# voiture.net
KiCad netlist of a schematic drawn in EAGLE
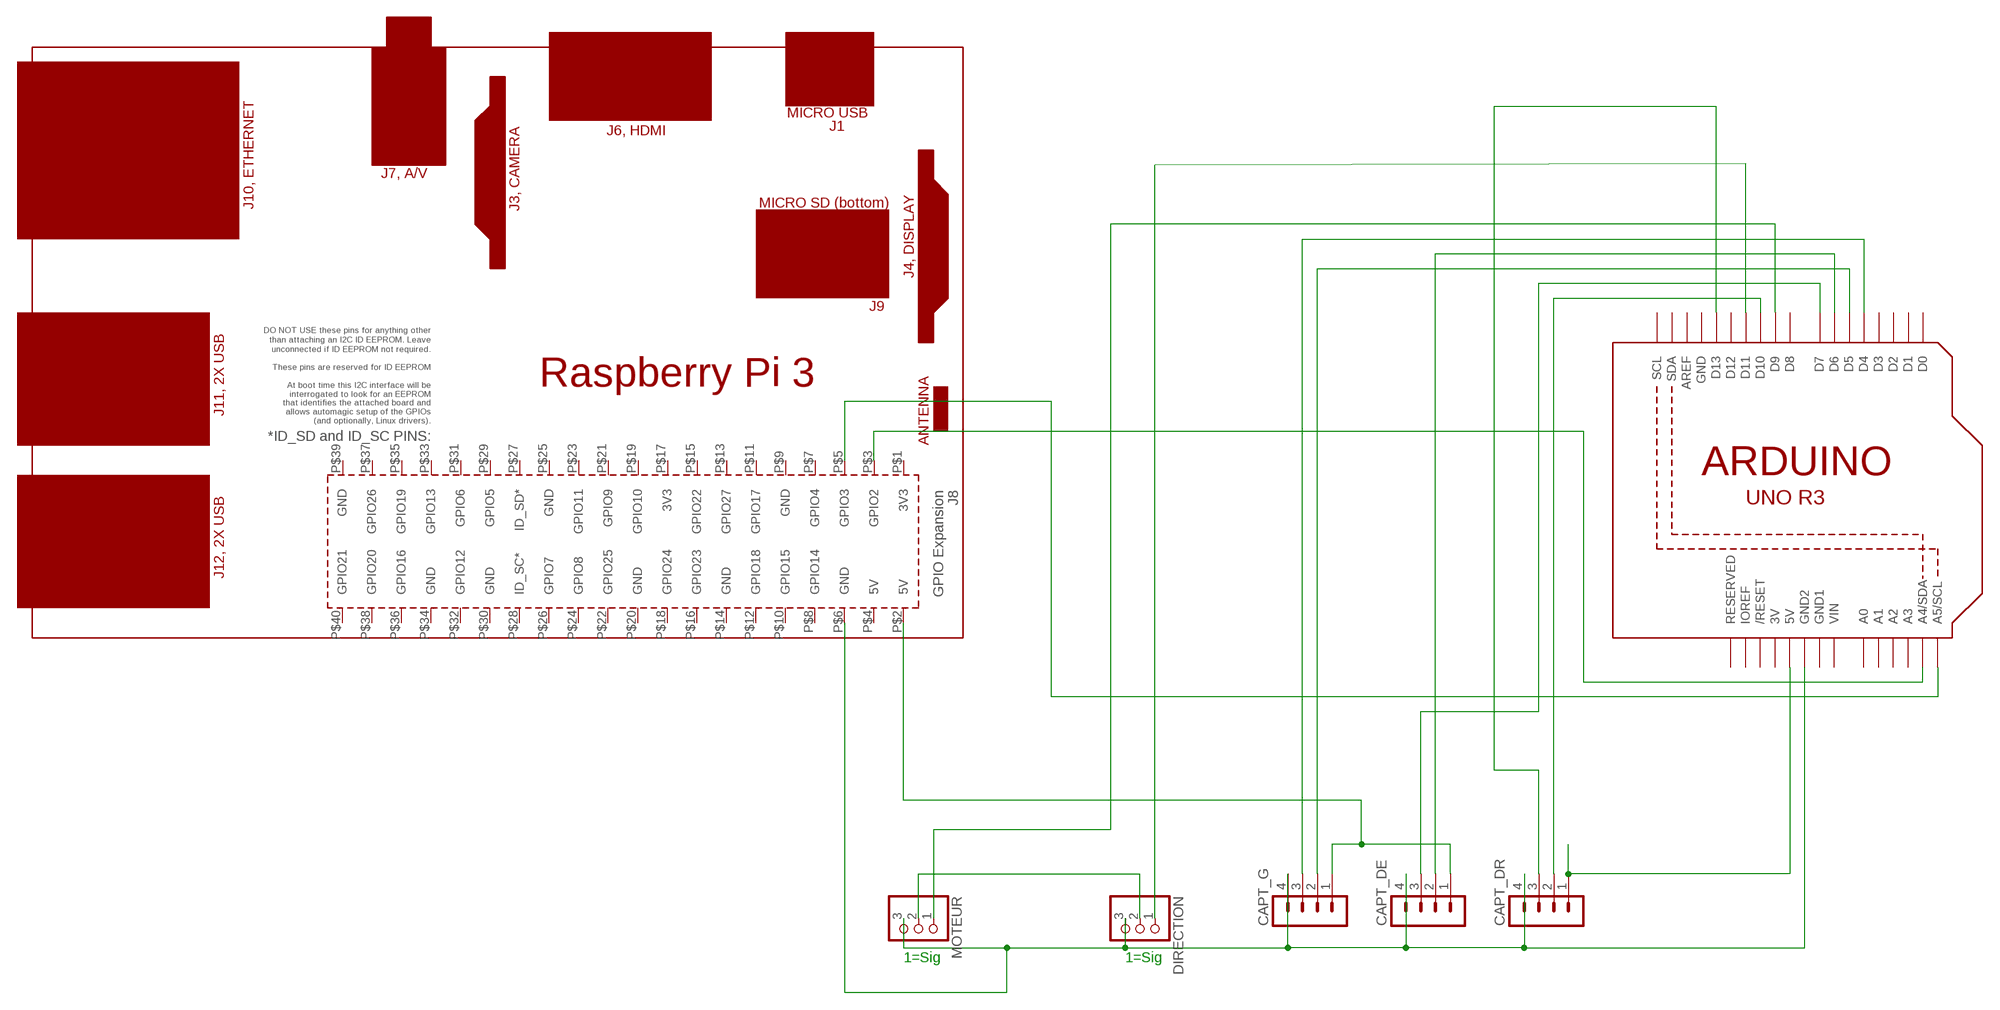
[diagram p0: schematic, sheet 1]

(export (version "E")
  (design (tool "Eeschema 10.0.6"))
  (components
    (comp (ref "CAPT_DE")
      (value "MA04-1")
      (footprint "eagle-import:MA04-1")
      (libsource (lib "eagle-import") (part "MA04-1"))
    )
    (comp (ref "CAPT_DR")
      (value "MA04-1")
      (footprint "eagle-import:MA04-1")
      (libsource (lib "eagle-import") (part "MA04-1"))
    )
    (comp (ref "CAPT_G")
      (value "MA04-1")
      (footprint "eagle-import:MA04-1")
      (libsource (lib "eagle-import") (part "MA04-1"))
    )
    (comp (ref "DIRECTION")
      (value "PINHD-1X3")
      (footprint "eagle-import:1X03")
      (libsource (lib "eagle-import") (part "PINHD-1X3"))
    )
    (comp (ref "MOTEUR")
      (value "PINHD-1X3")
      (footprint "eagle-import:1X03")
      (libsource (lib "eagle-import") (part "PINHD-1X3"))
    )
    (comp (ref "PCB1")
      (value "RPI3")
      (footprint "eagle-import:RPI3")
      (libsource (lib "eagle-import") (part "RPI3"))
    )
    (comp (ref "U1")
      (value "ARDUINOR3-BPLACE")
      (footprint "eagle-import:ARDUINOR3-BPLACE")
      (libsource (lib "eagle-import") (part "ARDUINOR3-BPLACE"))
    )
  )
  (nets
    (net (code "1") (name "/3V") (class "Default")
      (node (ref "U1") (pin "3V") (pinfunction "3V_3V") (pintype "power_in"))
    )
    (net (code "2") (name "/GND") (class "Default")
      (node (ref "U1") (pin "GND") (pinfunction "GND_GND") (pintype "power_in"))
    )
    (net (code "3") (name "/GND1") (class "Default")
      (node (ref "U1") (pin "GND1") (pinfunction "GND1_GND1") (pintype "power_in"))
    )
    (net (code "4") (name "/VIN") (class "Default")
      (node (ref "U1") (pin "VIN") (pinfunction "VIN_VIN") (pintype "power_in"))
    )
    (net (code "5") (name "Net-(CAPT_DE-Pad1)") (class "Default")
      (node (ref "CAPT_DE") (pin "1") (pinfunction "1_1") (pintype "passive"))
      (node (ref "CAPT_G") (pin "1") (pinfunction "1_1") (pintype "passive"))
      (node (ref "PCB1") (pin "P$2") (pinfunction "5V_P$2") (pintype "bidirectional"))
    )
    (net (code "6") (name "Net-(CAPT_DE-Pad2)") (class "Default")
      (node (ref "CAPT_DE") (pin "2") (pinfunction "2_2") (pintype "passive"))
      (node (ref "U1") (pin "D6") (pinfunction "D6_D6") (pintype "bidirectional"))
    )
    (net (code "7") (name "Net-(CAPT_DE-Pad3)") (class "Default")
      (node (ref "CAPT_DE") (pin "3") (pinfunction "3_3") (pintype "passive"))
      (node (ref "U1") (pin "D7") (pinfunction "D7_D7") (pintype "bidirectional"))
    )
    (net (code "8") (name "Net-(CAPT_DE-Pad4)") (class "Default")
      (node (ref "CAPT_DE") (pin "4") (pinfunction "4_4") (pintype "passive"))
      (node (ref "CAPT_DR") (pin "4") (pinfunction "4_4") (pintype "passive"))
      (node (ref "CAPT_G") (pin "4") (pinfunction "4_4") (pintype "passive"))
      (node (ref "DIRECTION") (pin "3") (pinfunction "3_3") (pintype "passive"))
      (node (ref "MOTEUR") (pin "3") (pinfunction "3_3") (pintype "passive"))
      (node (ref "PCB1") (pin "P$6") (pinfunction "GND_P$6") (pintype "bidirectional"))
      (node (ref "U1") (pin "GND2") (pinfunction "GND2_GND2") (pintype "power_in"))
    )
    (net (code "9") (name "Net-(CAPT_DR-Pad1)") (class "Default")
      (node (ref "CAPT_DR") (pin "1") (pinfunction "1_1") (pintype "passive"))
      (node (ref "U1") (pin "5V") (pinfunction "5V_5V") (pintype "power_in"))
    )
    (net (code "10") (name "Net-(CAPT_DR-Pad2)") (class "Default")
      (node (ref "CAPT_DR") (pin "2") (pinfunction "2_2") (pintype "passive"))
      (node (ref "U1") (pin "D10") (pinfunction "D10_D10") (pintype "bidirectional"))
    )
    (net (code "11") (name "Net-(CAPT_DR-Pad3)") (class "Default")
      (node (ref "CAPT_DR") (pin "3") (pinfunction "3_3") (pintype "passive"))
      (node (ref "U1") (pin "D13") (pinfunction "D13_D13") (pintype "bidirectional"))
    )
    (net (code "12") (name "Net-(CAPT_G-Pad2)") (class "Default")
      (node (ref "CAPT_G") (pin "2") (pinfunction "2_2") (pintype "passive"))
      (node (ref "U1") (pin "D5") (pinfunction "D5_D5") (pintype "bidirectional"))
    )
    (net (code "13") (name "Net-(CAPT_G-Pad3)") (class "Default")
      (node (ref "CAPT_G") (pin "3") (pinfunction "3_3") (pintype "passive"))
      (node (ref "U1") (pin "D4") (pinfunction "D4_D4") (pintype "bidirectional"))
    )
    (net (code "14") (name "Net-(DIRECTION-Pad1)") (class "Default")
      (node (ref "DIRECTION") (pin "1") (pinfunction "1_1") (pintype "passive"))
      (node (ref "U1") (pin "D11") (pinfunction "D11_D11") (pintype "bidirectional"))
    )
    (net (code "15") (name "Net-(DIRECTION-Pad2)") (class "Default")
      (node (ref "DIRECTION") (pin "2") (pinfunction "2_2") (pintype "passive"))
      (node (ref "MOTEUR") (pin "2") (pinfunction "2_2") (pintype "passive"))
    )
    (net (code "16") (name "Net-(MOTEUR-Pad1)") (class "Default")
      (node (ref "MOTEUR") (pin "1") (pinfunction "1_1") (pintype "passive"))
      (node (ref "U1") (pin "D9") (pinfunction "D9_D9") (pintype "bidirectional"))
    )
    (net (code "17") (name "Net-(PCB1-GPIO2)") (class "Default")
      (node (ref "PCB1") (pin "P$3") (pinfunction "GPIO2_P$3") (pintype "bidirectional"))
      (node (ref "U1") (pin "A4") (pinfunction "A4/SDA_A4") (pintype "bidirectional"))
    )
    (net (code "18") (name "Net-(PCB1-GPIO3)") (class "Default")
      (node (ref "PCB1") (pin "P$5") (pinfunction "GPIO3_P$5") (pintype "bidirectional"))
      (node (ref "U1") (pin "A5") (pinfunction "A5/SCL_A5") (pintype "bidirectional"))
    )
    (net (code "19") (name "unconnected-(PCB1-3V3-PadP$1)") (class "Default")
      (node (ref "PCB1") (pin "P$1") (pinfunction "3V3_P$1") (pintype "bidirectional"))
    )
    (net (code "20") (name "unconnected-(PCB1-3V3-PadP$17)") (class "Default")
      (node (ref "PCB1") (pin "P$17") (pinfunction "3V3_P$17") (pintype "bidirectional"))
    )
    (net (code "21") (name "unconnected-(PCB1-5V-PadP$4)") (class "Default")
      (node (ref "PCB1") (pin "P$4") (pinfunction "5V_P$4") (pintype "bidirectional"))
    )
    (net (code "22") (name "unconnected-(PCB1-GND-PadP$9)") (class "Default")
      (node (ref "PCB1") (pin "P$9") (pinfunction "GND_P$9") (pintype "bidirectional"))
    )
    (net (code "23") (name "unconnected-(PCB1-GND-PadP$14)") (class "Default")
      (node (ref "PCB1") (pin "P$14") (pinfunction "GND_P$14") (pintype "bidirectional"))
    )
    (net (code "24") (name "unconnected-(PCB1-GND-PadP$20)") (class "Default")
      (node (ref "PCB1") (pin "P$20") (pinfunction "GND_P$20") (pintype "bidirectional"))
    )
    (net (code "25") (name "unconnected-(PCB1-GND-PadP$25)") (class "Default")
      (node (ref "PCB1") (pin "P$25") (pinfunction "GND_P$25") (pintype "bidirectional"))
    )
    (net (code "26") (name "unconnected-(PCB1-GND-PadP$30)") (class "Default")
      (node (ref "PCB1") (pin "P$30") (pinfunction "GND_P$30") (pintype "bidirectional"))
    )
    (net (code "27") (name "unconnected-(PCB1-GND-PadP$34)") (class "Default")
      (node (ref "PCB1") (pin "P$34") (pinfunction "GND_P$34") (pintype "bidirectional"))
    )
    (net (code "28") (name "unconnected-(PCB1-GND-PadP$39)") (class "Default")
      (node (ref "PCB1") (pin "P$39") (pinfunction "GND_P$39") (pintype "bidirectional"))
    )
    (net (code "29") (name "unconnected-(PCB1-GPIO4-PadP$7)") (class "Default")
      (node (ref "PCB1") (pin "P$7") (pinfunction "GPIO4_P$7") (pintype "bidirectional"))
    )
    (net (code "30") (name "unconnected-(PCB1-GPIO5-PadP$29)") (class "Default")
      (node (ref "PCB1") (pin "P$29") (pinfunction "GPIO5_P$29") (pintype "bidirectional"))
    )
    (net (code "31") (name "unconnected-(PCB1-GPIO6-PadP$31)") (class "Default")
      (node (ref "PCB1") (pin "P$31") (pinfunction "GPIO6_P$31") (pintype "bidirectional"))
    )
    (net (code "32") (name "unconnected-(PCB1-GPIO7-PadP$26)") (class "Default")
      (node (ref "PCB1") (pin "P$26") (pinfunction "GPIO7_P$26") (pintype "bidirectional"))
    )
    (net (code "33") (name "unconnected-(PCB1-GPIO8-PadP$24)") (class "Default")
      (node (ref "PCB1") (pin "P$24") (pinfunction "GPIO8_P$24") (pintype "bidirectional"))
    )
    (net (code "34") (name "unconnected-(PCB1-GPIO9-PadP$21)") (class "Default")
      (node (ref "PCB1") (pin "P$21") (pinfunction "GPIO9_P$21") (pintype "bidirectional"))
    )
    (net (code "35") (name "unconnected-(PCB1-GPIO10-PadP$19)") (class "Default")
      (node (ref "PCB1") (pin "P$19") (pinfunction "GPIO10_P$19") (pintype "bidirectional"))
    )
    (net (code "36") (name "unconnected-(PCB1-GPIO11-PadP$23)") (class "Default")
      (node (ref "PCB1") (pin "P$23") (pinfunction "GPIO11_P$23") (pintype "bidirectional"))
    )
    (net (code "37") (name "unconnected-(PCB1-GPIO12-PadP$32)") (class "Default")
      (node (ref "PCB1") (pin "P$32") (pinfunction "GPIO12_P$32") (pintype "bidirectional"))
    )
    (net (code "38") (name "unconnected-(PCB1-GPIO13-PadP$33)") (class "Default")
      (node (ref "PCB1") (pin "P$33") (pinfunction "GPIO13_P$33") (pintype "bidirectional"))
    )
    (net (code "39") (name "unconnected-(PCB1-GPIO14-PadP$8)") (class "Default")
      (node (ref "PCB1") (pin "P$8") (pinfunction "GPIO14_P$8") (pintype "bidirectional"))
    )
    (net (code "40") (name "unconnected-(PCB1-GPIO15-PadP$10)") (class "Default")
      (node (ref "PCB1") (pin "P$10") (pinfunction "GPIO15_P$10") (pintype "bidirectional"))
    )
    (net (code "41") (name "unconnected-(PCB1-GPIO16-PadP$36)") (class "Default")
      (node (ref "PCB1") (pin "P$36") (pinfunction "GPIO16_P$36") (pintype "bidirectional"))
    )
    (net (code "42") (name "unconnected-(PCB1-GPIO17-PadP$11)") (class "Default")
      (node (ref "PCB1") (pin "P$11") (pinfunction "GPIO17_P$11") (pintype "bidirectional"))
    )
    (net (code "43") (name "unconnected-(PCB1-GPIO18-PadP$12)") (class "Default")
      (node (ref "PCB1") (pin "P$12") (pinfunction "GPIO18_P$12") (pintype "bidirectional"))
    )
    (net (code "44") (name "unconnected-(PCB1-GPIO19-PadP$35)") (class "Default")
      (node (ref "PCB1") (pin "P$35") (pinfunction "GPIO19_P$35") (pintype "bidirectional"))
    )
    (net (code "45") (name "unconnected-(PCB1-GPIO20-PadP$38)") (class "Default")
      (node (ref "PCB1") (pin "P$38") (pinfunction "GPIO20_P$38") (pintype "bidirectional"))
    )
    (net (code "46") (name "unconnected-(PCB1-GPIO21-PadP$40)") (class "Default")
      (node (ref "PCB1") (pin "P$40") (pinfunction "GPIO21_P$40") (pintype "bidirectional"))
    )
    (net (code "47") (name "unconnected-(PCB1-GPIO22-PadP$15)") (class "Default")
      (node (ref "PCB1") (pin "P$15") (pinfunction "GPIO22_P$15") (pintype "bidirectional"))
    )
    (net (code "48") (name "unconnected-(PCB1-GPIO23-PadP$16)") (class "Default")
      (node (ref "PCB1") (pin "P$16") (pinfunction "GPIO23_P$16") (pintype "bidirectional"))
    )
    (net (code "49") (name "unconnected-(PCB1-GPIO24-PadP$18)") (class "Default")
      (node (ref "PCB1") (pin "P$18") (pinfunction "GPIO24_P$18") (pintype "bidirectional"))
    )
    (net (code "50") (name "unconnected-(PCB1-GPIO25-PadP$22)") (class "Default")
      (node (ref "PCB1") (pin "P$22") (pinfunction "GPIO25_P$22") (pintype "bidirectional"))
    )
    (net (code "51") (name "unconnected-(PCB1-GPIO26-PadP$37)") (class "Default")
      (node (ref "PCB1") (pin "P$37") (pinfunction "GPIO26_P$37") (pintype "bidirectional"))
    )
    (net (code "52") (name "unconnected-(PCB1-GPIO27-PadP$13)") (class "Default")
      (node (ref "PCB1") (pin "P$13") (pinfunction "GPIO27_P$13") (pintype "bidirectional"))
    )
    (net (code "53") (name "unconnected-(PCB1-ID_SC*-PadP$28)") (class "Default")
      (node (ref "PCB1") (pin "P$28") (pinfunction "ID_SC*_P$28") (pintype "bidirectional"))
    )
    (net (code "54") (name "unconnected-(PCB1-ID_SD*-PadP$27)") (class "Default")
      (node (ref "PCB1") (pin "P$27") (pinfunction "ID_SD*_P$27") (pintype "bidirectional"))
    )
    (net (code "55") (name "unconnected-(U1-PadA0)") (class "Default")
      (node (ref "U1") (pin "A0") (pinfunction "A0_A0") (pintype "bidirectional"))
    )
    (net (code "56") (name "unconnected-(U1-PadA1)") (class "Default")
      (node (ref "U1") (pin "A1") (pinfunction "A1_A1") (pintype "bidirectional"))
    )
    (net (code "57") (name "unconnected-(U1-PadA2)") (class "Default")
      (node (ref "U1") (pin "A2") (pinfunction "A2_A2") (pintype "bidirectional"))
    )
    (net (code "58") (name "unconnected-(U1-PadA3)") (class "Default")
      (node (ref "U1") (pin "A3") (pinfunction "A3_A3") (pintype "bidirectional"))
    )
    (net (code "59") (name "unconnected-(U1-PadAREF)") (class "Default")
      (node (ref "U1") (pin "AREF") (pinfunction "AREF_AREF") (pintype "bidirectional"))
    )
    (net (code "60") (name "unconnected-(U1-PadD0)") (class "Default")
      (node (ref "U1") (pin "D0") (pinfunction "D0_D0") (pintype "bidirectional"))
    )
    (net (code "61") (name "unconnected-(U1-PadD1)") (class "Default")
      (node (ref "U1") (pin "D1") (pinfunction "D1_D1") (pintype "bidirectional"))
    )
    (net (code "62") (name "unconnected-(U1-PadD2)") (class "Default")
      (node (ref "U1") (pin "D2") (pinfunction "D2_D2") (pintype "bidirectional"))
    )
    (net (code "63") (name "unconnected-(U1-PadD3)") (class "Default")
      (node (ref "U1") (pin "D3") (pinfunction "D3_D3") (pintype "bidirectional"))
    )
    (net (code "64") (name "unconnected-(U1-PadD8)") (class "Default")
      (node (ref "U1") (pin "D8") (pinfunction "D8_D8") (pintype "bidirectional"))
    )
    (net (code "65") (name "unconnected-(U1-PadD12)") (class "Default")
      (node (ref "U1") (pin "D12") (pinfunction "D12_D12") (pintype "bidirectional"))
    )
    (net (code "66") (name "unconnected-(U1-PadIOREF)") (class "Default")
      (node (ref "U1") (pin "IOREF") (pinfunction "IOREF_IOREF") (pintype "output"))
    )
    (net (code "67") (name "unconnected-(U1-PadRESERVED)") (class "Default")
      (node (ref "U1") (pin "RESERVED") (pinfunction "RESERVED_RESERVED") (pintype "no_connect"))
    )
    (net (code "68") (name "unconnected-(U1-PadSCL)") (class "Default")
      (node (ref "U1") (pin "SCL") (pinfunction "SCL_SCL") (pintype "bidirectional"))
    )
    (net (code "69") (name "unconnected-(U1-PadSDA)") (class "Default")
      (node (ref "U1") (pin "SDA") (pinfunction "SDA_SDA") (pintype "bidirectional"))
    )
    (net (code "70") (name "unconnected-(U1-{slash}RESET-PadRESET)") (class "Default")
      (node (ref "U1") (pin "RESET") (pinfunction "/RESET_RESET") (pintype "bidirectional"))
    )
  )
)
